# Sheet1.net
KiCad netlist of a schematic drawn in Altium Designer
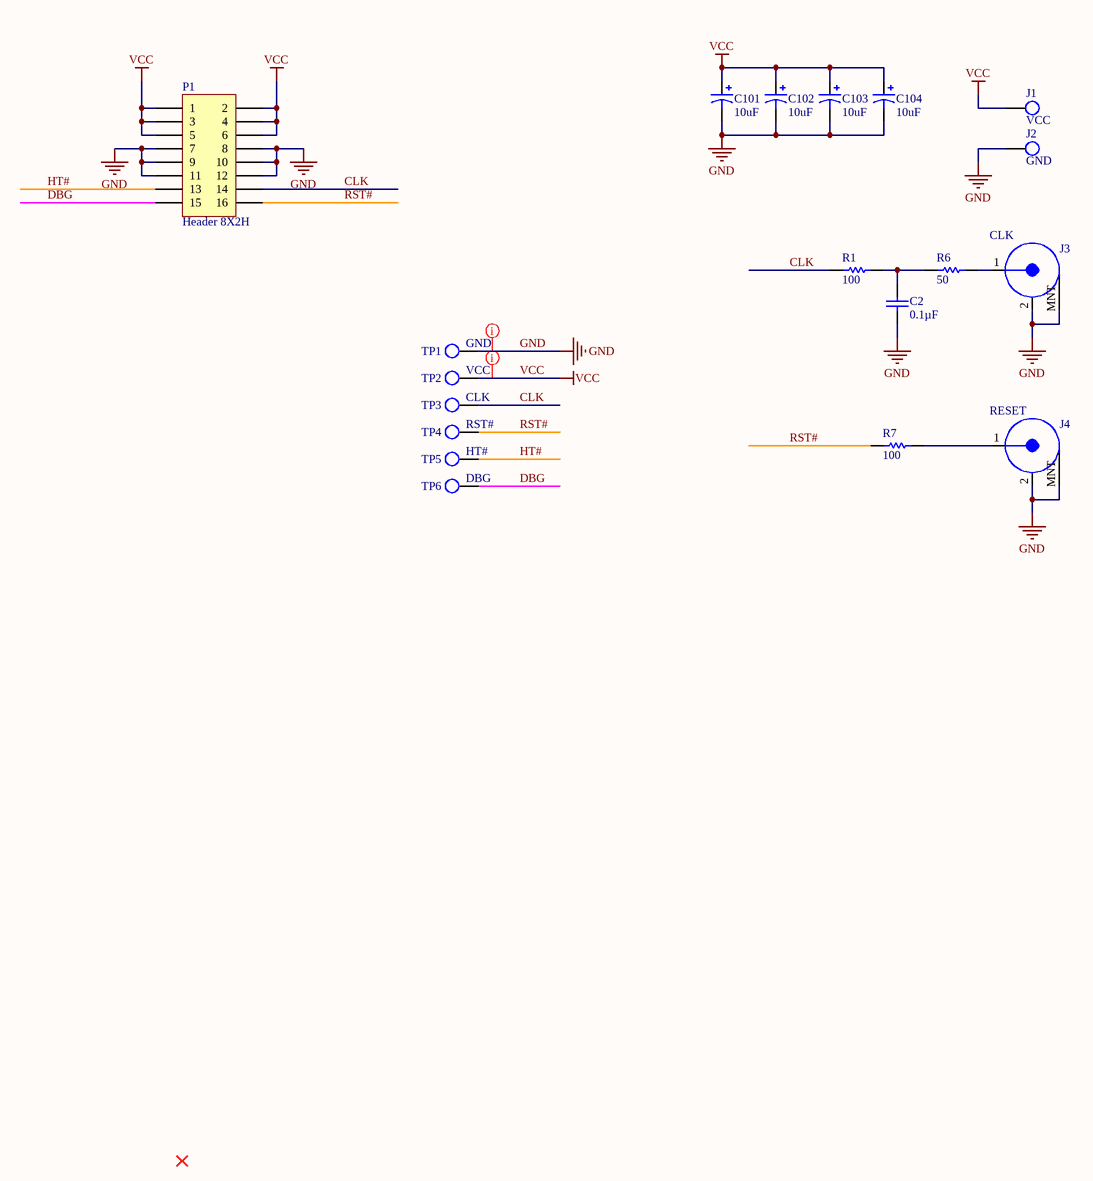
[diagram p0: Sheet1.SchDoc]

(export (version "E")
  (design (tool "Eeschema 10.0.6"))
  (components
    (comp (ref "C2")
      (value "K104K15X7RF5TL2")
      (footprint "VISH-K104K15X7RF5TL2")
      (description "Ceramic Capacitor, 100 nF, +/- 10%, 50 V, -55 to 125 degC, 2-Pin THD, RoHS, Tape and Reel")
      (fields
        (field (name "MANUFACTURER") "Vishay")
        (field (name "TOLERANCE") "±10%")
        (field (name "CAPACITANCE") "0.1µF")
      )
      (libsource (lib "Altium Content Vault") (part "CAP-NP-2"))
    )
    (comp (ref "C101")
      (value "10uF")
      (footprint "C5x7")
      (description "Polarized Capacitor")
      (fields (field (name "Comment") "Cap Pol5") (field (name "PUBLISHER") "Altium Limited"))
      (libsource (lib "Miscellaneous Devices") (part "Cap Pol5"))
    )
    (comp (ref "C102")
      (value "10uF")
      (footprint "C5x7")
      (description "Polarized Capacitor")
      (fields (field (name "Comment") "Cap Pol5") (field (name "PUBLISHER") "Altium Limited"))
      (libsource (lib "Miscellaneous Devices") (part "Cap Pol5"))
    )
    (comp (ref "C103")
      (value "10uF")
      (footprint "C5x7")
      (description "Polarized Capacitor")
      (fields (field (name "Comment") "Cap Pol5") (field (name "PUBLISHER") "Altium Limited"))
      (libsource (lib "Miscellaneous Devices") (part "Cap Pol5"))
    )
    (comp (ref "C104")
      (value "10uF")
      (footprint "C5x7")
      (description "Polarized Capacitor")
      (fields (field (name "Comment") "Cap Pol5") (field (name "PUBLISHER") "Altium Limited"))
      (libsource (lib "Miscellaneous Devices") (part "Cap Pol5"))
    )
    (comp (ref "J1")
      (value "VCC")
      (footprint "CT3151SP-2")
      (description "CONN BANANA JACK SOLDER RED")
      (libsource (lib "TP") (part "CT3151SP-2"))
    )
    (comp (ref "J2")
      (value "GND")
      (footprint "CT3151SP-0")
      (description "CONN BANANA JACK SOLDER BLACK")
      (libsource (lib "TP") (part "CT3151SP-0"))
    )
    (comp (ref "J3") (value "CLK") (footprint "BNC R/A") (libsource (lib "ModularPayload") (part "RF")))
    (comp (ref "J4") (value "RESET") (footprint "BNC R/A") (libsource (lib "ModularPayload") (part "RF")))
    (comp (ref "P1")
      (value "Header 8X2H")
      (footprint "HDR2X8H")
      (description "Header, 8-Pin, Dual row, Right Angle")
      (fields (field (name "PUBLISHER") "Altium Limited"))
      (libsource (lib "Miscellaneous Connectors") (part "Header 8X2H"))
    )
    (comp (ref "R1")
      (value "100")
      (footprint "AXIAL-0.3")
      (description "Resistor")
      (fields (field (name "Comment") "Res1") (field (name "PUBLISHER") "Altium Limited"))
      (libsource (lib "Miscellaneous Devices") (part "Res1"))
    )
    (comp (ref "R6")
      (value "50")
      (footprint "AXIAL-0.3")
      (description "Resistor")
      (fields (field (name "Comment") "Res1") (field (name "PUBLISHER") "Altium Limited"))
      (libsource (lib "Miscellaneous Devices") (part "Res1"))
    )
    (comp (ref "R7")
      (value "100")
      (footprint "AXIAL-0.3")
      (description "Resistor")
      (fields (field (name "Comment") "Res1") (field (name "PUBLISHER") "Altium Limited"))
      (libsource (lib "Miscellaneous Devices") (part "Res1"))
    )
    (comp (ref "TP1") (value "GND") (footprint "KSTN-5011_V") (libsource (lib "TP") (part "TP")))
    (comp (ref "TP2") (value "VCC") (footprint "KSTN-5011_V") (libsource (lib "TP") (part "TP")))
    (comp (ref "TP3") (value "CLK") (footprint "KSTN-5011_V") (libsource (lib "TP") (part "TP")))
    (comp (ref "TP4") (value "RST#") (footprint "KSTN-5011_V") (libsource (lib "TP") (part "TP")))
    (comp (ref "TP5") (value "HT#") (footprint "KSTN-5011_V") (libsource (lib "TP") (part "TP")))
    (comp (ref "TP6") (value "DBG") (footprint "KSTN-5011_V") (libsource (lib "TP") (part "TP")))
  )
  (nets
    (net (code "1") (name "/CLK") (class "Default")
      (node (ref "P1") (pin "14") (pinfunction "14_14") (pintype "passive"))
      (node (ref "R1") (pin "2") (pinfunction "2_2") (pintype "passive"))
      (node (ref "TP3") (pin "1") (pintype "passive"))
    )
    (net (code "2") (name "/DBG") (class "Default")
      (node (ref "P1") (pin "15") (pinfunction "15_15") (pintype "passive"))
      (node (ref "TP6") (pin "1") (pintype "passive"))
    )
    (net (code "3") (name "/HT#") (class "Default")
      (node (ref "P1") (pin "13") (pinfunction "13_13") (pintype "passive"))
      (node (ref "TP5") (pin "1") (pintype "passive"))
    )
    (net (code "4") (name "/RST#") (class "Default")
      (node (ref "P1") (pin "16") (pinfunction "16_16") (pintype "passive"))
      (node (ref "R7") (pin "2") (pinfunction "2_2") (pintype "passive"))
      (node (ref "TP4") (pin "1") (pintype "passive"))
    )
    (net (code "5") (name "GND") (class "Default")
      (node (ref "C101") (pin "2") (pinfunction "2_2") (pintype "passive"))
      (node (ref "C102") (pin "2") (pinfunction "2_2") (pintype "passive"))
      (node (ref "C103") (pin "2") (pinfunction "2_2") (pintype "passive"))
      (node (ref "C104") (pin "2") (pinfunction "2_2") (pintype "passive"))
      (node (ref "C2") (pin "2") (pinfunction "2_2") (pintype "passive"))
      (node (ref "J2") (pin "1") (pintype "passive"))
      (node (ref "J3") (pin "2") (pintype "passive"))
      (node (ref "J3") (pin "MNT") (pinfunction "MNT_MNT") (pintype "passive"))
      (node (ref "J4") (pin "2") (pintype "passive"))
      (node (ref "J4") (pin "MNT") (pinfunction "MNT_MNT") (pintype "passive"))
      (node (ref "P1") (pin "10") (pinfunction "10_10") (pintype "passive"))
      (node (ref "P1") (pin "11") (pinfunction "11_11") (pintype "passive"))
      (node (ref "P1") (pin "12") (pinfunction "12_12") (pintype "passive"))
      (node (ref "P1") (pin "7") (pinfunction "7_7") (pintype "passive"))
      (node (ref "P1") (pin "8") (pinfunction "8_8") (pintype "passive"))
      (node (ref "P1") (pin "9") (pinfunction "9_9") (pintype "passive"))
      (node (ref "TP1") (pin "1") (pintype "passive"))
    )
    (net (code "6") (name "Net-(C2-Pad1)") (class "Default")
      (node (ref "C2") (pin "1") (pinfunction "1_1") (pintype "passive"))
      (node (ref "R1") (pin "1") (pinfunction "1_1") (pintype "passive"))
      (node (ref "R6") (pin "2") (pinfunction "2_2") (pintype "passive"))
    )
    (net (code "7") (name "Net-(J3-Pad1)") (class "Default")
      (node (ref "J3") (pin "1") (pintype "passive"))
      (node (ref "R6") (pin "1") (pinfunction "1_1") (pintype "passive"))
    )
    (net (code "8") (name "Net-(J4-Pad1)") (class "Default")
      (node (ref "J4") (pin "1") (pintype "passive"))
      (node (ref "R7") (pin "1") (pinfunction "1_1") (pintype "passive"))
    )
    (net (code "9") (name "VCC") (class "Default")
      (node (ref "C101") (pin "1") (pinfunction "1_1") (pintype "passive"))
      (node (ref "C102") (pin "1") (pinfunction "1_1") (pintype "passive"))
      (node (ref "C103") (pin "1") (pinfunction "1_1") (pintype "passive"))
      (node (ref "C104") (pin "1") (pinfunction "1_1") (pintype "passive"))
      (node (ref "J1") (pin "1") (pintype "passive"))
      (node (ref "P1") (pin "1") (pinfunction "1_1") (pintype "passive"))
      (node (ref "P1") (pin "2") (pinfunction "2_2") (pintype "passive"))
      (node (ref "P1") (pin "3") (pinfunction "3_3") (pintype "passive"))
      (node (ref "P1") (pin "4") (pinfunction "4_4") (pintype "passive"))
      (node (ref "P1") (pin "5") (pinfunction "5_5") (pintype "passive"))
      (node (ref "P1") (pin "6") (pinfunction "6_6") (pintype "passive"))
      (node (ref "TP2") (pin "1") (pintype "passive"))
    )
  )
)
